# stm32f4_disc.net
KiCad netlist of a schematic drawn in EAGLE
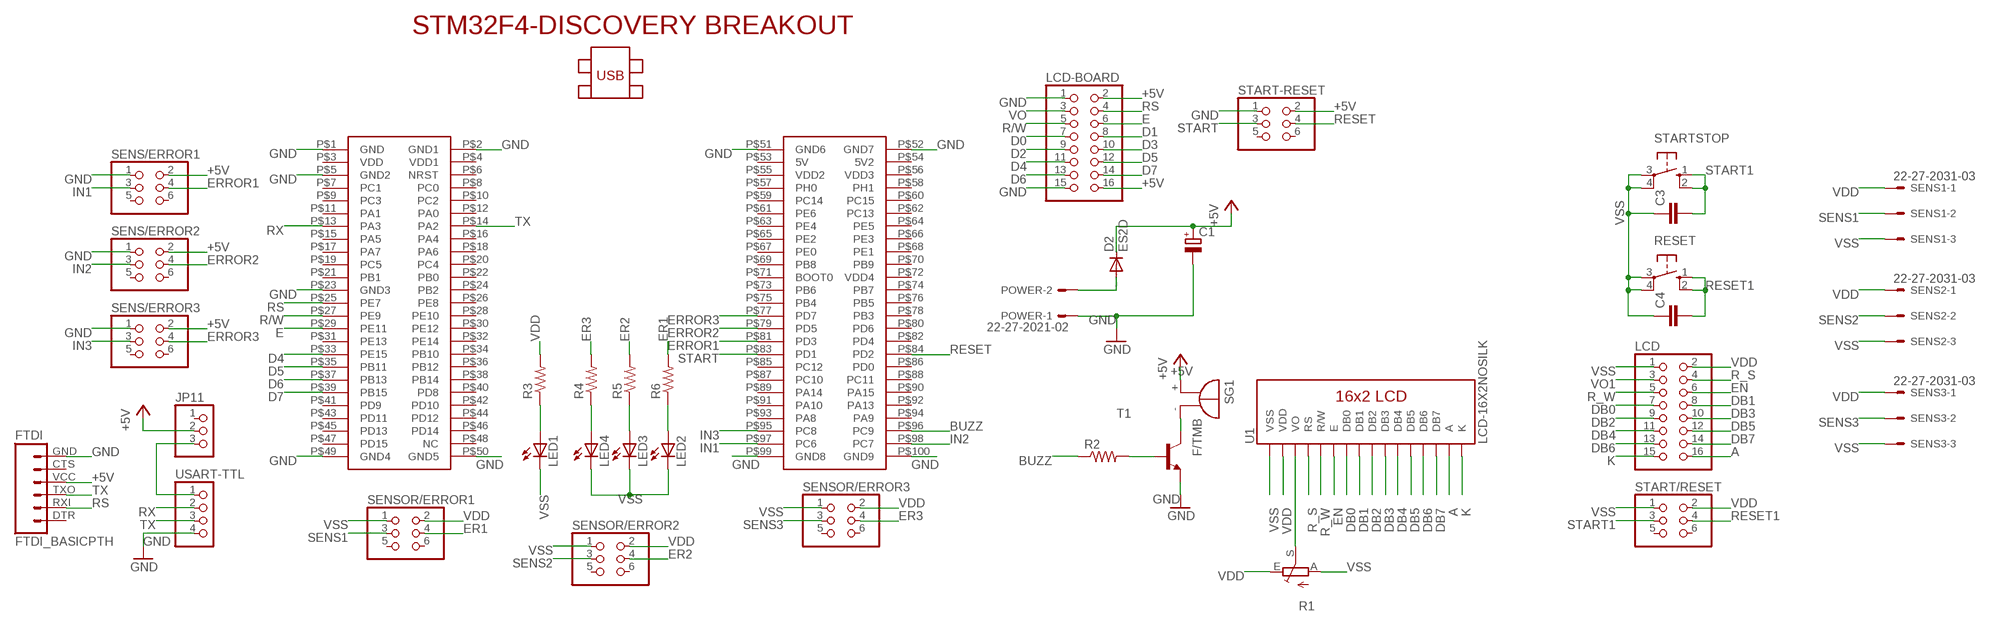
[diagram p0: schematic, sheet 1]

(export (version "E")
  (design (tool "Eeschema 10.0.6"))
  (components
    (comp (ref "C1")
      (value "CPOL-EU140CLH-1010")
      (footprint "eagle-import:140CLH-1010")
      (libsource (lib "eagle-import") (part "CPOL-EU140CLH-1010"))
    )
    (comp (ref "C3")
      (value "C-EUC0805")
      (footprint "eagle-import:C0805")
      (libsource (lib "eagle-import") (part "C-EUC0805"))
    )
    (comp (ref "C4")
      (value "C-EUC0805")
      (footprint "eagle-import:C0805")
      (libsource (lib "eagle-import") (part "C-EUC0805"))
    )
    (comp (ref "D2")
      (value "ES2D")
      (footprint "eagle-import:SMB")
      (libsource (lib "eagle-import") (part "ES2D"))
    )
    (comp (ref "FTDI")
      (value "FTDI_BASICPTH")
      (footprint "eagle-import:FTDI_BASIC")
      (libsource (lib "eagle-import") (part "FTDI_BASICPTH"))
    )
    (comp (ref "JP11")
      (value "PINHD-1X3")
      (footprint "eagle-import:1X03")
      (libsource (lib "eagle-import") (part "PINHD-1X3"))
    )
    (comp (ref "LCD")
      (value "PINHD-2X8")
      (footprint "eagle-import:2X08")
      (libsource (lib "eagle-import") (part "PINHD-2X8"))
    )
    (comp (ref "LCD-BOARD")
      (value "PINHD-2X8")
      (footprint "eagle-import:2X08")
      (libsource (lib "eagle-import") (part "PINHD-2X8"))
    )
    (comp (ref "LED1")
      (value "LED5MM")
      (footprint "eagle-import:LED5MM")
      (libsource (lib "eagle-import") (part "LED5MM"))
    )
    (comp (ref "LED2")
      (value "LED5MM")
      (footprint "eagle-import:LED5MM")
      (libsource (lib "eagle-import") (part "LED5MM"))
    )
    (comp (ref "LED3")
      (value "LED5MM")
      (footprint "eagle-import:LED5MM")
      (libsource (lib "eagle-import") (part "LED5MM"))
    )
    (comp (ref "LED4")
      (value "LED5MM")
      (footprint "eagle-import:LED5MM")
      (libsource (lib "eagle-import") (part "LED5MM"))
    )
    (comp (ref "POWER")
      (value "22-27-2021-02")
      (footprint "eagle-import:6410-02")
      (libsource (lib "eagle-import") (part "22-?-0227-2021"))
    )
    (comp (ref "R1")
      (value "TRIM_EU-CA6V")
      (footprint "eagle-import:CA6V")
      (libsource (lib "eagle-import") (part "TRIM_EU-CA6V"))
    )
    (comp (ref "R2")
      (value "R-US_R0805")
      (footprint "eagle-import:R0805")
      (libsource (lib "eagle-import") (part "R-US_R0805"))
    )
    (comp (ref "R3")
      (value "R-US_R0805")
      (footprint "eagle-import:R0805")
      (libsource (lib "eagle-import") (part "R-US_R0805"))
    )
    (comp (ref "R4")
      (value "R-US_R0805")
      (footprint "eagle-import:R0805")
      (libsource (lib "eagle-import") (part "R-US_R0805"))
    )
    (comp (ref "R5")
      (value "R-US_R0805")
      (footprint "eagle-import:R0805")
      (libsource (lib "eagle-import") (part "R-US_R0805"))
    )
    (comp (ref "R6")
      (value "R-US_R0805")
      (footprint "eagle-import:R0805")
      (libsource (lib "eagle-import") (part "R-US_R0805"))
    )
    (comp (ref "RESET")
      (value "40-XX")
      (footprint "eagle-import:B3F-40XX")
      (fields (field (name "MF") "OMRON COMPONENTS USA") (field (name "MPN") "B3F-4000"))
      (libsource (lib "eagle-import") (part "40-XX"))
    )
    (comp (ref "SENS/ERROR1")
      (value "PINHD-2X3")
      (footprint "eagle-import:2X03")
      (libsource (lib "eagle-import") (part "PINHD-2X3"))
    )
    (comp (ref "SENS/ERROR2")
      (value "PINHD-2X3")
      (footprint "eagle-import:2X03")
      (libsource (lib "eagle-import") (part "PINHD-2X3"))
    )
    (comp (ref "SENS/ERROR3")
      (value "PINHD-2X3")
      (footprint "eagle-import:2X03")
      (libsource (lib "eagle-import") (part "PINHD-2X3"))
    )
    (comp (ref "SENS1")
      (value "22-27-2031-03")
      (footprint "eagle-import:6410-03")
      (libsource (lib "eagle-import") (part "22-?-0327-2031"))
    )
    (comp (ref "SENS2")
      (value "22-27-2031-03")
      (footprint "eagle-import:6410-03")
      (libsource (lib "eagle-import") (part "22-?-0327-2031"))
    )
    (comp (ref "SENS3")
      (value "22-27-2031-03")
      (footprint "eagle-import:6410-03")
      (libsource (lib "eagle-import") (part "22-?-0327-2031"))
    )
    (comp (ref "SENSOR/ERROR1")
      (value "PINHD-2X3")
      (footprint "eagle-import:2X03")
      (libsource (lib "eagle-import") (part "PINHD-2X3"))
    )
    (comp (ref "SENSOR/ERROR2")
      (value "PINHD-2X3")
      (footprint "eagle-import:2X03")
      (libsource (lib "eagle-import") (part "PINHD-2X3"))
    )
    (comp (ref "SENSOR/ERROR3")
      (value "PINHD-2X3")
      (footprint "eagle-import:2X03")
      (libsource (lib "eagle-import") (part "PINHD-2X3"))
    )
    (comp (ref "SG1")
      (value "F/TMB")
      (footprint "eagle-import:F_TMB")
      (libsource (lib "eagle-import") (part "F/TMB"))
    )
    (comp (ref "START-RESET")
      (value "PINHD-2X3")
      (footprint "eagle-import:2X03")
      (libsource (lib "eagle-import") (part "PINHD-2X3"))
    )
    (comp (ref "START/RESET")
      (value "PINHD-2X3")
      (footprint "eagle-import:2X03")
      (libsource (lib "eagle-import") (part "PINHD-2X3"))
    )
    (comp (ref "STARTSTOP")
      (value "40-XX")
      (footprint "eagle-import:B3F-40XX")
      (fields (field (name "MF") "OMRON COMPONENTS USA") (field (name "MPN") "B3F-4000"))
      (libsource (lib "eagle-import") (part "40-XX"))
    )
    (comp (ref "T1")
      (value "-NPN-SOT23-EBC")
      (footprint "eagle-import:SOT23-EBC")
      (libsource (lib "eagle-import") (part "-NPN-SOT23-EBC"))
    )
    (comp (ref "U$1")
      (value "STM32F4-DISCOVERY")
      (footprint "eagle-import:STM32F4-DISCOVERY")
      (libsource (lib "eagle-import") (part "STM32F4-DISCOVERY"))
    )
    (comp (ref "U1")
      (value "LCD-16X2NOSILK")
      (footprint "eagle-import:LCD-16X2_NOSILK")
      (libsource (lib "eagle-import") (part "LCD-16X2NOSILK"))
    )
    (comp (ref "USART-TTL")
      (value "PINHD-1X4")
      (footprint "eagle-import:1X04")
      (libsource (lib "eagle-import") (part "PINHD-1X4"))
    )
  )
  (nets
    (net (code "1") (name "+5V") (class "Default")
      (node (ref "C1") (pin "+") (pinfunction "+_+") (pintype "passive"))
      (node (ref "D2") (pin "C") (pinfunction "C_C") (pintype "passive"))
      (node (ref "FTDI") (pin "VCC") (pinfunction "4_VCC") (pintype "passive"))
      (node (ref "JP11") (pin "2") (pinfunction "2_2") (pintype "passive"))
      (node (ref "LCD-BOARD") (pin "16") (pinfunction "16_16") (pintype "passive"))
      (node (ref "LCD-BOARD") (pin "2") (pinfunction "2_2") (pintype "passive"))
      (node (ref "SENS/ERROR1") (pin "2") (pinfunction "2_2") (pintype "passive"))
      (node (ref "SENS/ERROR2") (pin "2") (pinfunction "2_2") (pintype "passive"))
      (node (ref "SENS/ERROR3") (pin "2") (pinfunction "2_2") (pintype "passive"))
      (node (ref "SG1") (pin "+") (pinfunction "+_+") (pintype "passive"))
      (node (ref "START-RESET") (pin "2") (pinfunction "2_2") (pintype "passive"))
    )
    (net (code "2") (name "/A") (class "Default")
      (node (ref "LCD") (pin "16") (pinfunction "16_16") (pintype "passive"))
      (node (ref "U1") (pin "15") (pinfunction "A_15") (pintype "power_in"))
    )
    (net (code "3") (name "/BUZZ") (class "Default")
      (node (ref "R2") (pin "1") (pinfunction "1_1") (pintype "passive"))
      (node (ref "U$1") (pin "P$96") (pinfunction "PC9_P$96") (pintype "bidirectional"))
    )
    (net (code "4") (name "/D0") (class "Default")
      (node (ref "LCD-BOARD") (pin "7") (pinfunction "7_7") (pintype "passive"))
    )
    (net (code "5") (name "/D1") (class "Default")
      (node (ref "LCD-BOARD") (pin "8") (pinfunction "8_8") (pintype "passive"))
    )
    (net (code "6") (name "/D2") (class "Default")
      (node (ref "LCD-BOARD") (pin "9") (pinfunction "9_9") (pintype "passive"))
    )
    (net (code "7") (name "/D3") (class "Default")
      (node (ref "LCD-BOARD") (pin "10") (pinfunction "10_10") (pintype "passive"))
    )
    (net (code "8") (name "/D4") (class "Default")
      (node (ref "LCD-BOARD") (pin "11") (pinfunction "11_11") (pintype "passive"))
      (node (ref "U$1") (pin "P$33") (pinfunction "PE15_P$33") (pintype "bidirectional"))
    )
    (net (code "9") (name "/D5") (class "Default")
      (node (ref "LCD-BOARD") (pin "12") (pinfunction "12_12") (pintype "passive"))
      (node (ref "U$1") (pin "P$35") (pinfunction "PB11_P$35") (pintype "bidirectional"))
    )
    (net (code "10") (name "/D6") (class "Default")
      (node (ref "LCD-BOARD") (pin "13") (pinfunction "13_13") (pintype "passive"))
      (node (ref "U$1") (pin "P$37") (pinfunction "PB13_P$37") (pintype "bidirectional"))
    )
    (net (code "11") (name "/D7") (class "Default")
      (node (ref "LCD-BOARD") (pin "14") (pinfunction "14_14") (pintype "passive"))
      (node (ref "U$1") (pin "P$39") (pinfunction "PB15_P$39") (pintype "bidirectional"))
    )
    (net (code "12") (name "/DB0") (class "Default")
      (node (ref "LCD") (pin "7") (pinfunction "7_7") (pintype "passive"))
      (node (ref "U1") (pin "7") (pinfunction "DB0_7") (pintype "bidirectional"))
    )
    (net (code "13") (name "/DB1") (class "Default")
      (node (ref "LCD") (pin "8") (pinfunction "8_8") (pintype "passive"))
      (node (ref "U1") (pin "8") (pinfunction "DB1_8") (pintype "bidirectional"))
    )
    (net (code "14") (name "/DB2") (class "Default")
      (node (ref "LCD") (pin "9") (pinfunction "9_9") (pintype "passive"))
      (node (ref "U1") (pin "9") (pinfunction "DB2_9") (pintype "bidirectional"))
    )
    (net (code "15") (name "/DB3") (class "Default")
      (node (ref "LCD") (pin "10") (pinfunction "10_10") (pintype "passive"))
      (node (ref "U1") (pin "10") (pinfunction "DB3_10") (pintype "bidirectional"))
    )
    (net (code "16") (name "/DB4") (class "Default")
      (node (ref "LCD") (pin "11") (pinfunction "11_11") (pintype "passive"))
      (node (ref "U1") (pin "11") (pinfunction "DB4_11") (pintype "bidirectional"))
    )
    (net (code "17") (name "/DB5") (class "Default")
      (node (ref "LCD") (pin "12") (pinfunction "12_12") (pintype "passive"))
      (node (ref "U1") (pin "12") (pinfunction "DB5_12") (pintype "bidirectional"))
    )
    (net (code "18") (name "/DB6") (class "Default")
      (node (ref "LCD") (pin "13") (pinfunction "13_13") (pintype "passive"))
      (node (ref "U1") (pin "13") (pinfunction "DB6_13") (pintype "bidirectional"))
    )
    (net (code "19") (name "/DB7") (class "Default")
      (node (ref "LCD") (pin "14") (pinfunction "14_14") (pintype "passive"))
      (node (ref "U1") (pin "14") (pinfunction "DB7_14") (pintype "bidirectional"))
    )
    (net (code "20") (name "/E") (class "Default")
      (node (ref "LCD-BOARD") (pin "6") (pinfunction "6_6") (pintype "passive"))
      (node (ref "U$1") (pin "P$29") (pinfunction "PE11_P$29") (pintype "bidirectional"))
    )
    (net (code "21") (name "/EN") (class "Default")
      (node (ref "LCD") (pin "6") (pinfunction "6_6") (pintype "passive"))
      (node (ref "U1") (pin "6") (pinfunction "E_6") (pintype "input"))
    )
    (net (code "22") (name "/ER1") (class "Default")
      (node (ref "R6") (pin "2") (pinfunction "2_2") (pintype "passive"))
      (node (ref "SENSOR/ERROR1") (pin "4") (pinfunction "4_4") (pintype "passive"))
    )
    (net (code "23") (name "/ER2") (class "Default")
      (node (ref "R5") (pin "2") (pinfunction "2_2") (pintype "passive"))
      (node (ref "SENSOR/ERROR2") (pin "4") (pinfunction "4_4") (pintype "passive"))
    )
    (net (code "24") (name "/ER3") (class "Default")
      (node (ref "R4") (pin "2") (pinfunction "2_2") (pintype "passive"))
      (node (ref "SENSOR/ERROR3") (pin "4") (pinfunction "4_4") (pintype "passive"))
    )
    (net (code "25") (name "/ERROR1") (class "Default")
      (node (ref "SENS/ERROR1") (pin "4") (pinfunction "4_4") (pintype "passive"))
      (node (ref "U$1") (pin "P$81") (pinfunction "PD3_P$81") (pintype "bidirectional"))
    )
    (net (code "26") (name "/ERROR2") (class "Default")
      (node (ref "SENS/ERROR2") (pin "4") (pinfunction "4_4") (pintype "passive"))
      (node (ref "U$1") (pin "P$79") (pinfunction "PD5_P$79") (pintype "bidirectional"))
    )
    (net (code "27") (name "/ERROR3") (class "Default")
      (node (ref "SENS/ERROR3") (pin "4") (pinfunction "4_4") (pintype "passive"))
      (node (ref "U$1") (pin "P$77") (pinfunction "PD7_P$77") (pintype "bidirectional"))
    )
    (net (code "28") (name "/IN1") (class "Default")
      (node (ref "SENS/ERROR1") (pin "3") (pinfunction "3_3") (pintype "passive"))
      (node (ref "U$1") (pin "P$97") (pinfunction "PC6_P$97") (pintype "bidirectional"))
    )
    (net (code "29") (name "/IN2") (class "Default")
      (node (ref "SENS/ERROR2") (pin "3") (pinfunction "3_3") (pintype "passive"))
      (node (ref "U$1") (pin "P$98") (pinfunction "PC7_P$98") (pintype "bidirectional"))
    )
    (net (code "30") (name "/IN3") (class "Default")
      (node (ref "SENS/ERROR3") (pin "3") (pinfunction "3_3") (pintype "passive"))
      (node (ref "U$1") (pin "P$95") (pinfunction "PC8_P$95") (pintype "bidirectional"))
    )
    (net (code "31") (name "/K") (class "Default")
      (node (ref "LCD") (pin "15") (pinfunction "15_15") (pintype "passive"))
      (node (ref "U1") (pin "16") (pinfunction "K_16") (pintype "power_in"))
    )
    (net (code "32") (name "/RESET") (class "Default")
      (node (ref "START-RESET") (pin "4") (pinfunction "4_4") (pintype "passive"))
      (node (ref "U$1") (pin "P$84") (pinfunction "PD2_P$84") (pintype "bidirectional"))
    )
    (net (code "33") (name "/RESET1") (class "Default")
      (node (ref "C4") (pin "2") (pinfunction "2_2") (pintype "passive"))
      (node (ref "RESET") (pin "1") (pinfunction "S_1") (pintype "passive"))
      (node (ref "RESET") (pin "2") (pinfunction "S1_2") (pintype "passive"))
      (node (ref "START/RESET") (pin "4") (pinfunction "4_4") (pintype "passive"))
    )
    (net (code "34") (name "/RS") (class "Default")
      (node (ref "FTDI") (pin "RXI") (pinfunction "2_RXI") (pintype "passive"))
      (node (ref "LCD-BOARD") (pin "4") (pinfunction "4_4") (pintype "passive"))
      (node (ref "U$1") (pin "P$25") (pinfunction "PE7_P$25") (pintype "bidirectional"))
    )
    (net (code "35") (name "/RX") (class "Default")
      (node (ref "U$1") (pin "P$13") (pinfunction "PA3_P$13") (pintype "bidirectional"))
      (node (ref "USART-TTL") (pin "2") (pinfunction "2_2") (pintype "passive"))
    )
    (net (code "36") (name "/R_S") (class "Default")
      (node (ref "LCD") (pin "4") (pinfunction "4_4") (pintype "passive"))
      (node (ref "U1") (pin "4") (pinfunction "RS_4") (pintype "input"))
    )
    (net (code "37") (name "/R_W") (class "Default")
      (node (ref "LCD") (pin "5") (pinfunction "5_5") (pintype "passive"))
      (node (ref "U1") (pin "5") (pinfunction "R/W_5") (pintype "input"))
    )
    (net (code "38") (name "/R{slash}W") (class "Default")
      (node (ref "LCD-BOARD") (pin "5") (pinfunction "5_5") (pintype "passive"))
      (node (ref "U$1") (pin "P$27") (pinfunction "PE9_P$27") (pintype "bidirectional"))
    )
    (net (code "39") (name "/SENS1") (class "Default")
      (node (ref "SENS1") (pin "2") (pinfunction "S_2") (pintype "passive"))
      (node (ref "SENSOR/ERROR1") (pin "3") (pinfunction "3_3") (pintype "passive"))
    )
    (net (code "40") (name "/SENS2") (class "Default")
      (node (ref "SENS2") (pin "2") (pinfunction "S_2") (pintype "passive"))
      (node (ref "SENSOR/ERROR2") (pin "3") (pinfunction "3_3") (pintype "passive"))
    )
    (net (code "41") (name "/SENS3") (class "Default")
      (node (ref "SENS3") (pin "2") (pinfunction "S_2") (pintype "passive"))
      (node (ref "SENSOR/ERROR3") (pin "3") (pinfunction "3_3") (pintype "passive"))
    )
    (net (code "42") (name "/START") (class "Default")
      (node (ref "START-RESET") (pin "3") (pinfunction "3_3") (pintype "passive"))
      (node (ref "U$1") (pin "P$83") (pinfunction "PD1_P$83") (pintype "bidirectional"))
    )
    (net (code "43") (name "/START1") (class "Default")
      (node (ref "C3") (pin "2") (pinfunction "2_2") (pintype "passive"))
      (node (ref "START/RESET") (pin "3") (pinfunction "3_3") (pintype "passive"))
      (node (ref "STARTSTOP") (pin "1") (pinfunction "S_1") (pintype "passive"))
      (node (ref "STARTSTOP") (pin "2") (pinfunction "S1_2") (pintype "passive"))
    )
    (net (code "44") (name "/TX") (class "Default")
      (node (ref "FTDI") (pin "TXO") (pinfunction "3_TXO") (pintype "passive"))
      (node (ref "U$1") (pin "P$14") (pinfunction "PA2_P$14") (pintype "bidirectional"))
      (node (ref "USART-TTL") (pin "3") (pinfunction "3_3") (pintype "passive"))
    )
    (net (code "45") (name "/VDD") (class "Default")
      (node (ref "LCD") (pin "2") (pinfunction "2_2") (pintype "passive"))
      (node (ref "R1") (pin "E") (pinfunction "E_E") (pintype "passive"))
      (node (ref "R3") (pin "2") (pinfunction "2_2") (pintype "passive"))
      (node (ref "SENS1") (pin "1") (pinfunction "S_1") (pintype "passive"))
      (node (ref "SENS2") (pin "1") (pinfunction "S_1") (pintype "passive"))
      (node (ref "SENS3") (pin "1") (pinfunction "S_1") (pintype "passive"))
      (node (ref "SENSOR/ERROR1") (pin "2") (pinfunction "2_2") (pintype "passive"))
      (node (ref "SENSOR/ERROR2") (pin "2") (pinfunction "2_2") (pintype "passive"))
      (node (ref "SENSOR/ERROR3") (pin "2") (pinfunction "2_2") (pintype "passive"))
      (node (ref "START/RESET") (pin "2") (pinfunction "2_2") (pintype "passive"))
      (node (ref "U1") (pin "2") (pinfunction "VDD_2") (pintype "power_in"))
    )
    (net (code "46") (name "/VO") (class "Default")
      (node (ref "LCD-BOARD") (pin "3") (pinfunction "3_3") (pintype "passive"))
    )
    (net (code "47") (name "/VO1") (class "Default")
      (node (ref "LCD") (pin "3") (pinfunction "3_3") (pintype "passive"))
    )
    (net (code "48") (name "/VSS") (class "Default")
      (node (ref "C3") (pin "1") (pinfunction "1_1") (pintype "passive"))
      (node (ref "C4") (pin "1") (pinfunction "1_1") (pintype "passive"))
      (node (ref "LCD") (pin "1") (pinfunction "1_1") (pintype "passive"))
      (node (ref "LED1") (pin "K") (pinfunction "C_K") (pintype "passive"))
      (node (ref "LED2") (pin "K") (pinfunction "C_K") (pintype "passive"))
      (node (ref "LED3") (pin "K") (pinfunction "C_K") (pintype "passive"))
      (node (ref "LED4") (pin "K") (pinfunction "C_K") (pintype "passive"))
      (node (ref "R1") (pin "A") (pinfunction "A_A") (pintype "passive"))
      (node (ref "RESET") (pin "3") (pinfunction "P_3") (pintype "passive"))
      (node (ref "RESET") (pin "4") (pinfunction "P1_4") (pintype "passive"))
      (node (ref "SENS1") (pin "3") (pinfunction "S_3") (pintype "passive"))
      (node (ref "SENS2") (pin "3") (pinfunction "S_3") (pintype "passive"))
      (node (ref "SENS3") (pin "3") (pinfunction "S_3") (pintype "passive"))
      (node (ref "SENSOR/ERROR1") (pin "1") (pinfunction "1_1") (pintype "passive"))
      (node (ref "SENSOR/ERROR2") (pin "1") (pinfunction "1_1") (pintype "passive"))
      (node (ref "SENSOR/ERROR3") (pin "1") (pinfunction "1_1") (pintype "passive"))
      (node (ref "START/RESET") (pin "1") (pinfunction "1_1") (pintype "passive"))
      (node (ref "STARTSTOP") (pin "3") (pinfunction "P_3") (pintype "passive"))
      (node (ref "STARTSTOP") (pin "4") (pinfunction "P1_4") (pintype "passive"))
      (node (ref "U1") (pin "1") (pinfunction "VSS_1") (pintype "power_in"))
    )
    (net (code "49") (name "GND") (class "Default")
      (node (ref "C1") (pin "-") (pinfunction "-_-") (pintype "passive"))
      (node (ref "FTDI") (pin "GND") (pinfunction "6_GND") (pintype "passive"))
      (node (ref "LCD-BOARD") (pin "1") (pinfunction "1_1") (pintype "passive"))
      (node (ref "LCD-BOARD") (pin "15") (pinfunction "15_15") (pintype "passive"))
      (node (ref "POWER") (pin "1") (pinfunction "S_1") (pintype "passive"))
      (node (ref "SENS/ERROR1") (pin "1") (pinfunction "1_1") (pintype "passive"))
      (node (ref "SENS/ERROR2") (pin "1") (pinfunction "1_1") (pintype "passive"))
      (node (ref "SENS/ERROR3") (pin "1") (pinfunction "1_1") (pintype "passive"))
      (node (ref "START-RESET") (pin "1") (pinfunction "1_1") (pintype "passive"))
      (node (ref "T1") (pin "E") (pinfunction "E_E") (pintype "passive"))
      (node (ref "U$1") (pin "P$1") (pinfunction "GND_P$1") (pintype "bidirectional"))
      (node (ref "U$1") (pin "P$100") (pinfunction "GND9_P$100") (pintype "bidirectional"))
      (node (ref "U$1") (pin "P$2") (pinfunction "GND1_P$2") (pintype "bidirectional"))
      (node (ref "U$1") (pin "P$23") (pinfunction "GND3_P$23") (pintype "bidirectional"))
      (node (ref "U$1") (pin "P$49") (pinfunction "GND4_P$49") (pintype "bidirectional"))
      (node (ref "U$1") (pin "P$5") (pinfunction "GND2_P$5") (pintype "bidirectional"))
      (node (ref "U$1") (pin "P$50") (pinfunction "GND5_P$50") (pintype "bidirectional"))
      (node (ref "U$1") (pin "P$51") (pinfunction "GND6_P$51") (pintype "bidirectional"))
      (node (ref "U$1") (pin "P$52") (pinfunction "GND7_P$52") (pintype "bidirectional"))
      (node (ref "U$1") (pin "P$99") (pinfunction "GND8_P$99") (pintype "bidirectional"))
      (node (ref "USART-TTL") (pin "4") (pinfunction "4_4") (pintype "passive"))
    )
    (net (code "50") (name "Net-(JP11-Pad3)") (class "Default")
      (node (ref "JP11") (pin "3") (pinfunction "3_3") (pintype "passive"))
      (node (ref "USART-TTL") (pin "1") (pinfunction "1_1") (pintype "passive"))
    )
    (net (code "51") (name "Net-(LED1-PadA)") (class "Default")
      (node (ref "LED1") (pin "A") (pinfunction "A_A") (pintype "passive"))
      (node (ref "R3") (pin "1") (pinfunction "1_1") (pintype "passive"))
    )
    (net (code "52") (name "Net-(LED2-PadA)") (class "Default")
      (node (ref "LED2") (pin "A") (pinfunction "A_A") (pintype "passive"))
      (node (ref "R6") (pin "1") (pinfunction "1_1") (pintype "passive"))
    )
    (net (code "53") (name "Net-(LED3-PadA)") (class "Default")
      (node (ref "LED3") (pin "A") (pinfunction "A_A") (pintype "passive"))
      (node (ref "R5") (pin "1") (pinfunction "1_1") (pintype "passive"))
    )
    (net (code "54") (name "Net-(LED4-PadA)") (class "Default")
      (node (ref "LED4") (pin "A") (pinfunction "A_A") (pintype "passive"))
      (node (ref "R4") (pin "1") (pinfunction "1_1") (pintype "passive"))
    )
    (net (code "55") (name "Net-(POWERB-S)") (class "Default")
      (node (ref "D2") (pin "A") (pinfunction "A_A") (pintype "passive"))
      (node (ref "POWER") (pin "2") (pinfunction "S_2") (pintype "passive"))
    )
    (net (code "56") (name "Net-(R2-Pad2)") (class "Default")
      (node (ref "R2") (pin "2") (pinfunction "2_2") (pintype "passive"))
      (node (ref "T1") (pin "B") (pinfunction "B_B") (pintype "passive"))
    )
    (net (code "57") (name "Net-(SG1-Pad-)") (class "Default")
      (node (ref "SG1") (pin "-") (pinfunction "-_-") (pintype "passive"))
      (node (ref "T1") (pin "C") (pinfunction "C_C") (pintype "passive"))
    )
    (net (code "58") (name "Net-(U1-VO)") (class "Default")
      (node (ref "R1") (pin "S") (pinfunction "S_S") (pintype "passive"))
      (node (ref "U1") (pin "3") (pinfunction "VO_3") (pintype "bidirectional"))
    )
    (net (code "59") (name "unconnected-(FTDI-1-PadDTR)") (class "Default")
      (node (ref "FTDI") (pin "DTR") (pinfunction "1_DTR") (pintype "passive"))
    )
    (net (code "60") (name "unconnected-(FTDI-5-PadCTS)") (class "Default")
      (node (ref "FTDI") (pin "CTS") (pinfunction "5_CTS") (pintype "passive"))
    )
    (net (code "61") (name "unconnected-(JP11-Pad1)") (class "Default")
      (node (ref "JP11") (pin "1") (pinfunction "1_1") (pintype "passive"))
    )
    (net (code "62") (name "unconnected-(SENS/ERROR1-Pad5)") (class "Default")
      (node (ref "SENS/ERROR1") (pin "5") (pinfunction "5_5") (pintype "passive"))
    )
    (net (code "63") (name "unconnected-(SENS/ERROR1-Pad6)") (class "Default")
      (node (ref "SENS/ERROR1") (pin "6") (pinfunction "6_6") (pintype "passive"))
    )
    (net (code "64") (name "unconnected-(SENS/ERROR2-Pad5)") (class "Default")
      (node (ref "SENS/ERROR2") (pin "5") (pinfunction "5_5") (pintype "passive"))
    )
    (net (code "65") (name "unconnected-(SENS/ERROR2-Pad6)") (class "Default")
      (node (ref "SENS/ERROR2") (pin "6") (pinfunction "6_6") (pintype "passive"))
    )
    (net (code "66") (name "unconnected-(SENS/ERROR3-Pad5)") (class "Default")
      (node (ref "SENS/ERROR3") (pin "5") (pinfunction "5_5") (pintype "passive"))
    )
    (net (code "67") (name "unconnected-(SENS/ERROR3-Pad6)") (class "Default")
      (node (ref "SENS/ERROR3") (pin "6") (pinfunction "6_6") (pintype "passive"))
    )
    (net (code "68") (name "unconnected-(SENSOR/ERROR1-Pad5)") (class "Default")
      (node (ref "SENSOR/ERROR1") (pin "5") (pinfunction "5_5") (pintype "passive"))
    )
    (net (code "69") (name "unconnected-(SENSOR/ERROR1-Pad6)") (class "Default")
      (node (ref "SENSOR/ERROR1") (pin "6") (pinfunction "6_6") (pintype "passive"))
    )
    (net (code "70") (name "unconnected-(SENSOR/ERROR2-Pad5)") (class "Default")
      (node (ref "SENSOR/ERROR2") (pin "5") (pinfunction "5_5") (pintype "passive"))
    )
    (net (code "71") (name "unconnected-(SENSOR/ERROR2-Pad6)") (class "Default")
      (node (ref "SENSOR/ERROR2") (pin "6") (pinfunction "6_6") (pintype "passive"))
    )
    (net (code "72") (name "unconnected-(SENSOR/ERROR3-Pad5)") (class "Default")
      (node (ref "SENSOR/ERROR3") (pin "5") (pinfunction "5_5") (pintype "passive"))
    )
    (net (code "73") (name "unconnected-(SENSOR/ERROR3-Pad6)") (class "Default")
      (node (ref "SENSOR/ERROR3") (pin "6") (pinfunction "6_6") (pintype "passive"))
    )
    (net (code "74") (name "unconnected-(START-RESET-Pad5)") (class "Default")
      (node (ref "START-RESET") (pin "5") (pinfunction "5_5") (pintype "passive"))
    )
    (net (code "75") (name "unconnected-(START-RESET-Pad6)") (class "Default")
      (node (ref "START-RESET") (pin "6") (pinfunction "6_6") (pintype "passive"))
    )
    (net (code "76") (name "unconnected-(START/RESET-Pad5)") (class "Default")
      (node (ref "START/RESET") (pin "5") (pinfunction "5_5") (pintype "passive"))
    )
    (net (code "77") (name "unconnected-(START/RESET-Pad6)") (class "Default")
      (node (ref "START/RESET") (pin "6") (pinfunction "6_6") (pintype "passive"))
    )
    (net (code "78") (name "unconnected-(U$1-5V-PadP$53)") (class "Default")
      (node (ref "U$1") (pin "P$53") (pinfunction "5V_P$53") (pintype "bidirectional"))
    )
    (net (code "79") (name "unconnected-(U$1-5V2-PadP$54)") (class "Default")
      (node (ref "U$1") (pin "P$54") (pinfunction "5V2_P$54") (pintype "bidirectional"))
    )
    (net (code "80") (name "unconnected-(U$1-BOOT0-PadP$71)") (class "Default")
      (node (ref "U$1") (pin "P$71") (pinfunction "BOOT0_P$71") (pintype "bidirectional"))
    )
    (net (code "81") (name "unconnected-(U$1-NC-PadP$48)") (class "Default")
      (node (ref "U$1") (pin "P$48") (pinfunction "NC_P$48") (pintype "bidirectional"))
    )
    (net (code "82") (name "unconnected-(U$1-NRST-PadP$6)") (class "Default")
      (node (ref "U$1") (pin "P$6") (pinfunction "NRST_P$6") (pintype "bidirectional"))
    )
    (net (code "83") (name "unconnected-(U$1-PA0-PadP$12)") (class "Default")
      (node (ref "U$1") (pin "P$12") (pinfunction "PA0_P$12") (pintype "bidirectional"))
    )
    (net (code "84") (name "unconnected-(U$1-PA1-PadP$11)") (class "Default")
      (node (ref "U$1") (pin "P$11") (pinfunction "PA1_P$11") (pintype "bidirectional"))
    )
    (net (code "85") (name "unconnected-(U$1-PA4-PadP$16)") (class "Default")
      (node (ref "U$1") (pin "P$16") (pinfunction "PA4_P$16") (pintype "bidirectional"))
    )
    (net (code "86") (name "unconnected-(U$1-PA5-PadP$15)") (class "Default")
      (node (ref "U$1") (pin "P$15") (pinfunction "PA5_P$15") (pintype "bidirectional"))
    )
    (net (code "87") (name "unconnected-(U$1-PA6-PadP$18)") (class "Default")
      (node (ref "U$1") (pin "P$18") (pinfunction "PA6_P$18") (pintype "bidirectional"))
    )
    (net (code "88") (name "unconnected-(U$1-PA7-PadP$17)") (class "Default")
      (node (ref "U$1") (pin "P$17") (pinfunction "PA7_P$17") (pintype "bidirectional"))
    )
    (net (code "89") (name "unconnected-(U$1-PA8-PadP$93)") (class "Default")
      (node (ref "U$1") (pin "P$93") (pinfunction "PA8_P$93") (pintype "bidirectional"))
    )
    (net (code "90") (name "unconnected-(U$1-PA9-PadP$94)") (class "Default")
      (node (ref "U$1") (pin "P$94") (pinfunction "PA9_P$94") (pintype "bidirectional"))
    )
    (net (code "91") (name "unconnected-(U$1-PA10-PadP$91)") (class "Default")
      (node (ref "U$1") (pin "P$91") (pinfunction "PA10_P$91") (pintype "bidirectional"))
    )
    (net (code "92") (name "unconnected-(U$1-PA13-PadP$92)") (class "Default")
      (node (ref "U$1") (pin "P$92") (pinfunction "PA13_P$92") (pintype "bidirectional"))
    )
    (net (code "93") (name "unconnected-(U$1-PA14-PadP$89)") (class "Default")
      (node (ref "U$1") (pin "P$89") (pinfunction "PA14_P$89") (pintype "bidirectional"))
    )
    (net (code "94") (name "unconnected-(U$1-PA15-PadP$90)") (class "Default")
      (node (ref "U$1") (pin "P$90") (pinfunction "PA15_P$90") (pintype "bidirectional"))
    )
    (net (code "95") (name "unconnected-(U$1-PB0-PadP$22)") (class "Default")
      (node (ref "U$1") (pin "P$22") (pinfunction "PB0_P$22") (pintype "bidirectional"))
    )
    (net (code "96") (name "unconnected-(U$1-PB1-PadP$21)") (class "Default")
      (node (ref "U$1") (pin "P$21") (pinfunction "PB1_P$21") (pintype "bidirectional"))
    )
    (net (code "97") (name "unconnected-(U$1-PB2-PadP$24)") (class "Default")
      (node (ref "U$1") (pin "P$24") (pinfunction "PB2_P$24") (pintype "bidirectional"))
    )
    (net (code "98") (name "unconnected-(U$1-PB3-PadP$78)") (class "Default")
      (node (ref "U$1") (pin "P$78") (pinfunction "PB3_P$78") (pintype "bidirectional"))
    )
    (net (code "99") (name "unconnected-(U$1-PB4-PadP$75)") (class "Default")
      (node (ref "U$1") (pin "P$75") (pinfunction "PB4_P$75") (pintype "bidirectional"))
    )
    (net (code "100") (name "unconnected-(U$1-PB5-PadP$76)") (class "Default")
      (node (ref "U$1") (pin "P$76") (pinfunction "PB5_P$76") (pintype "bidirectional"))
    )
    (net (code "101") (name "unconnected-(U$1-PB6-PadP$73)") (class "Default")
      (node (ref "U$1") (pin "P$73") (pinfunction "PB6_P$73") (pintype "bidirectional"))
    )
    (net (code "102") (name "unconnected-(U$1-PB7-PadP$74)") (class "Default")
      (node (ref "U$1") (pin "P$74") (pinfunction "PB7_P$74") (pintype "bidirectional"))
    )
    (net (code "103") (name "unconnected-(U$1-PB8-PadP$69)") (class "Default")
      (node (ref "U$1") (pin "P$69") (pinfunction "PB8_P$69") (pintype "bidirectional"))
    )
    (net (code "104") (name "unconnected-(U$1-PB9-PadP$70)") (class "Default")
      (node (ref "U$1") (pin "P$70") (pinfunction "PB9_P$70") (pintype "bidirectional"))
    )
    (net (code "105") (name "unconnected-(U$1-PB10-PadP$34)") (class "Default")
      (node (ref "U$1") (pin "P$34") (pinfunction "PB10_P$34") (pintype "bidirectional"))
    )
    (net (code "106") (name "unconnected-(U$1-PB12-PadP$36)") (class "Default")
      (node (ref "U$1") (pin "P$36") (pinfunction "PB12_P$36") (pintype "bidirectional"))
    )
    (net (code "107") (name "unconnected-(U$1-PB14-PadP$38)") (class "Default")
      (node (ref "U$1") (pin "P$38") (pinfunction "PB14_P$38") (pintype "bidirectional"))
    )
    (net (code "108") (name "unconnected-(U$1-PC0-PadP$8)") (class "Default")
      (node (ref "U$1") (pin "P$8") (pinfunction "PC0_P$8") (pintype "bidirectional"))
    )
    (net (code "109") (name "unconnected-(U$1-PC1-PadP$7)") (class "Default")
      (node (ref "U$1") (pin "P$7") (pinfunction "PC1_P$7") (pintype "bidirectional"))
    )
    (net (code "110") (name "unconnected-(U$1-PC2-PadP$10)") (class "Default")
      (node (ref "U$1") (pin "P$10") (pinfunction "PC2_P$10") (pintype "bidirectional"))
    )
    (net (code "111") (name "unconnected-(U$1-PC3-PadP$9)") (class "Default")
      (node (ref "U$1") (pin "P$9") (pinfunction "PC3_P$9") (pintype "bidirectional"))
    )
    (net (code "112") (name "unconnected-(U$1-PC4-PadP$20)") (class "Default")
      (node (ref "U$1") (pin "P$20") (pinfunction "PC4_P$20") (pintype "bidirectional"))
    )
    (net (code "113") (name "unconnected-(U$1-PC5-PadP$19)") (class "Default")
      (node (ref "U$1") (pin "P$19") (pinfunction "PC5_P$19") (pintype "bidirectional"))
    )
    (net (code "114") (name "unconnected-(U$1-PC10-PadP$87)") (class "Default")
      (node (ref "U$1") (pin "P$87") (pinfunction "PC10_P$87") (pintype "bidirectional"))
    )
    (net (code "115") (name "unconnected-(U$1-PC11-PadP$88)") (class "Default")
      (node (ref "U$1") (pin "P$88") (pinfunction "PC11_P$88") (pintype "bidirectional"))
    )
    (net (code "116") (name "unconnected-(U$1-PC12-PadP$85)") (class "Default")
      (node (ref "U$1") (pin "P$85") (pinfunction "PC12_P$85") (pintype "bidirectional"))
    )
    (net (code "117") (name "unconnected-(U$1-PC13-PadP$62)") (class "Default")
      (node (ref "U$1") (pin "P$62") (pinfunction "PC13_P$62") (pintype "bidirectional"))
    )
    (net (code "118") (name "unconnected-(U$1-PC14-PadP$59)") (class "Default")
      (node (ref "U$1") (pin "P$59") (pinfunction "PC14_P$59") (pintype "bidirectional"))
    )
    (net (code "119") (name "unconnected-(U$1-PC15-PadP$60)") (class "Default")
      (node (ref "U$1") (pin "P$60") (pinfunction "PC15_P$60") (pintype "bidirectional"))
    )
    (net (code "120") (name "unconnected-(U$1-PD0-PadP$86)") (class "Default")
      (node (ref "U$1") (pin "P$86") (pinfunction "PD0_P$86") (pintype "bidirectional"))
    )
    (net (code "121") (name "unconnected-(U$1-PD4-PadP$82)") (class "Default")
      (node (ref "U$1") (pin "P$82") (pinfunction "PD4_P$82") (pintype "bidirectional"))
    )
    (net (code "122") (name "unconnected-(U$1-PD6-PadP$80)") (class "Default")
      (node (ref "U$1") (pin "P$80") (pinfunction "PD6_P$80") (pintype "bidirectional"))
    )
    (net (code "123") (name "unconnected-(U$1-PD8-PadP$40)") (class "Default")
      (node (ref "U$1") (pin "P$40") (pinfunction "PD8_P$40") (pintype "bidirectional"))
    )
    (net (code "124") (name "unconnected-(U$1-PD9-PadP$41)") (class "Default")
      (node (ref "U$1") (pin "P$41") (pinfunction "PD9_P$41") (pintype "bidirectional"))
    )
    (net (code "125") (name "unconnected-(U$1-PD10-PadP$42)") (class "Default")
      (node (ref "U$1") (pin "P$42") (pinfunction "PD10_P$42") (pintype "bidirectional"))
    )
    (net (code "126") (name "unconnected-(U$1-PD11-PadP$43)") (class "Default")
      (node (ref "U$1") (pin "P$43") (pinfunction "PD11_P$43") (pintype "bidirectional"))
    )
    (net (code "127") (name "unconnected-(U$1-PD12-PadP$44)") (class "Default")
      (node (ref "U$1") (pin "P$44") (pinfunction "PD12_P$44") (pintype "bidirectional"))
    )
    (net (code "128") (name "unconnected-(U$1-PD13-PadP$45)") (class "Default")
      (node (ref "U$1") (pin "P$45") (pinfunction "PD13_P$45") (pintype "bidirectional"))
    )
    (net (code "129") (name "unconnected-(U$1-PD14-PadP$46)") (class "Default")
      (node (ref "U$1") (pin "P$46") (pinfunction "PD14_P$46") (pintype "bidirectional"))
    )
    (net (code "130") (name "unconnected-(U$1-PD15-PadP$47)") (class "Default")
      (node (ref "U$1") (pin "P$47") (pinfunction "PD15_P$47") (pintype "bidirectional"))
    )
    (net (code "131") (name "unconnected-(U$1-PE0-PadP$67)") (class "Default")
      (node (ref "U$1") (pin "P$67") (pinfunction "PE0_P$67") (pintype "bidirectional"))
    )
    (net (code "132") (name "unconnected-(U$1-PE1-PadP$68)") (class "Default")
      (node (ref "U$1") (pin "P$68") (pinfunction "PE1_P$68") (pintype "bidirectional"))
    )
    (net (code "133") (name "unconnected-(U$1-PE2-PadP$65)") (class "Default")
      (node (ref "U$1") (pin "P$65") (pinfunction "PE2_P$65") (pintype "bidirectional"))
    )
    (net (code "134") (name "unconnected-(U$1-PE3-PadP$66)") (class "Default")
      (node (ref "U$1") (pin "P$66") (pinfunction "PE3_P$66") (pintype "bidirectional"))
    )
    (net (code "135") (name "unconnected-(U$1-PE4-PadP$63)") (class "Default")
      (node (ref "U$1") (pin "P$63") (pinfunction "PE4_P$63") (pintype "bidirectional"))
    )
    (net (code "136") (name "unconnected-(U$1-PE5-PadP$64)") (class "Default")
      (node (ref "U$1") (pin "P$64") (pinfunction "PE5_P$64") (pintype "bidirectional"))
    )
    (net (code "137") (name "unconnected-(U$1-PE6-PadP$61)") (class "Default")
      (node (ref "U$1") (pin "P$61") (pinfunction "PE6_P$61") (pintype "bidirectional"))
    )
    (net (code "138") (name "unconnected-(U$1-PE8-PadP$26)") (class "Default")
      (node (ref "U$1") (pin "P$26") (pinfunction "PE8_P$26") (pintype "bidirectional"))
    )
    (net (code "139") (name "unconnected-(U$1-PE10-PadP$28)") (class "Default")
      (node (ref "U$1") (pin "P$28") (pinfunction "PE10_P$28") (pintype "bidirectional"))
    )
    (net (code "140") (name "unconnected-(U$1-PE12-PadP$30)") (class "Default")
      (node (ref "U$1") (pin "P$30") (pinfunction "PE12_P$30") (pintype "bidirectional"))
    )
    (net (code "141") (name "unconnected-(U$1-PE13-PadP$31)") (class "Default")
      (node (ref "U$1") (pin "P$31") (pinfunction "PE13_P$31") (pintype "bidirectional"))
    )
    (net (code "142") (name "unconnected-(U$1-PE14-PadP$32)") (class "Default")
      (node (ref "U$1") (pin "P$32") (pinfunction "PE14_P$32") (pintype "bidirectional"))
    )
    (net (code "143") (name "unconnected-(U$1-PH0-PadP$57)") (class "Default")
      (node (ref "U$1") (pin "P$57") (pinfunction "PH0_P$57") (pintype "bidirectional"))
    )
    (net (code "144") (name "unconnected-(U$1-PH1-PadP$58)") (class "Default")
      (node (ref "U$1") (pin "P$58") (pinfunction "PH1_P$58") (pintype "bidirectional"))
    )
    (net (code "145") (name "unconnected-(U$1-VDD-PadP$3)") (class "Default")
      (node (ref "U$1") (pin "P$3") (pinfunction "VDD_P$3") (pintype "bidirectional"))
    )
    (net (code "146") (name "unconnected-(U$1-VDD1-PadP$4)") (class "Default")
      (node (ref "U$1") (pin "P$4") (pinfunction "VDD1_P$4") (pintype "bidirectional"))
    )
    (net (code "147") (name "unconnected-(U$1-VDD2-PadP$55)") (class "Default")
      (node (ref "U$1") (pin "P$55") (pinfunction "VDD2_P$55") (pintype "bidirectional"))
    )
    (net (code "148") (name "unconnected-(U$1-VDD3-PadP$56)") (class "Default")
      (node (ref "U$1") (pin "P$56") (pinfunction "VDD3_P$56") (pintype "bidirectional"))
    )
    (net (code "149") (name "unconnected-(U$1-VDD4-PadP$72)") (class "Default")
      (node (ref "U$1") (pin "P$72") (pinfunction "VDD4_P$72") (pintype "bidirectional"))
    )
  )
)
